# Pizza_BASE.net
KiCad netlist of a schematic drawn in Altium Designer
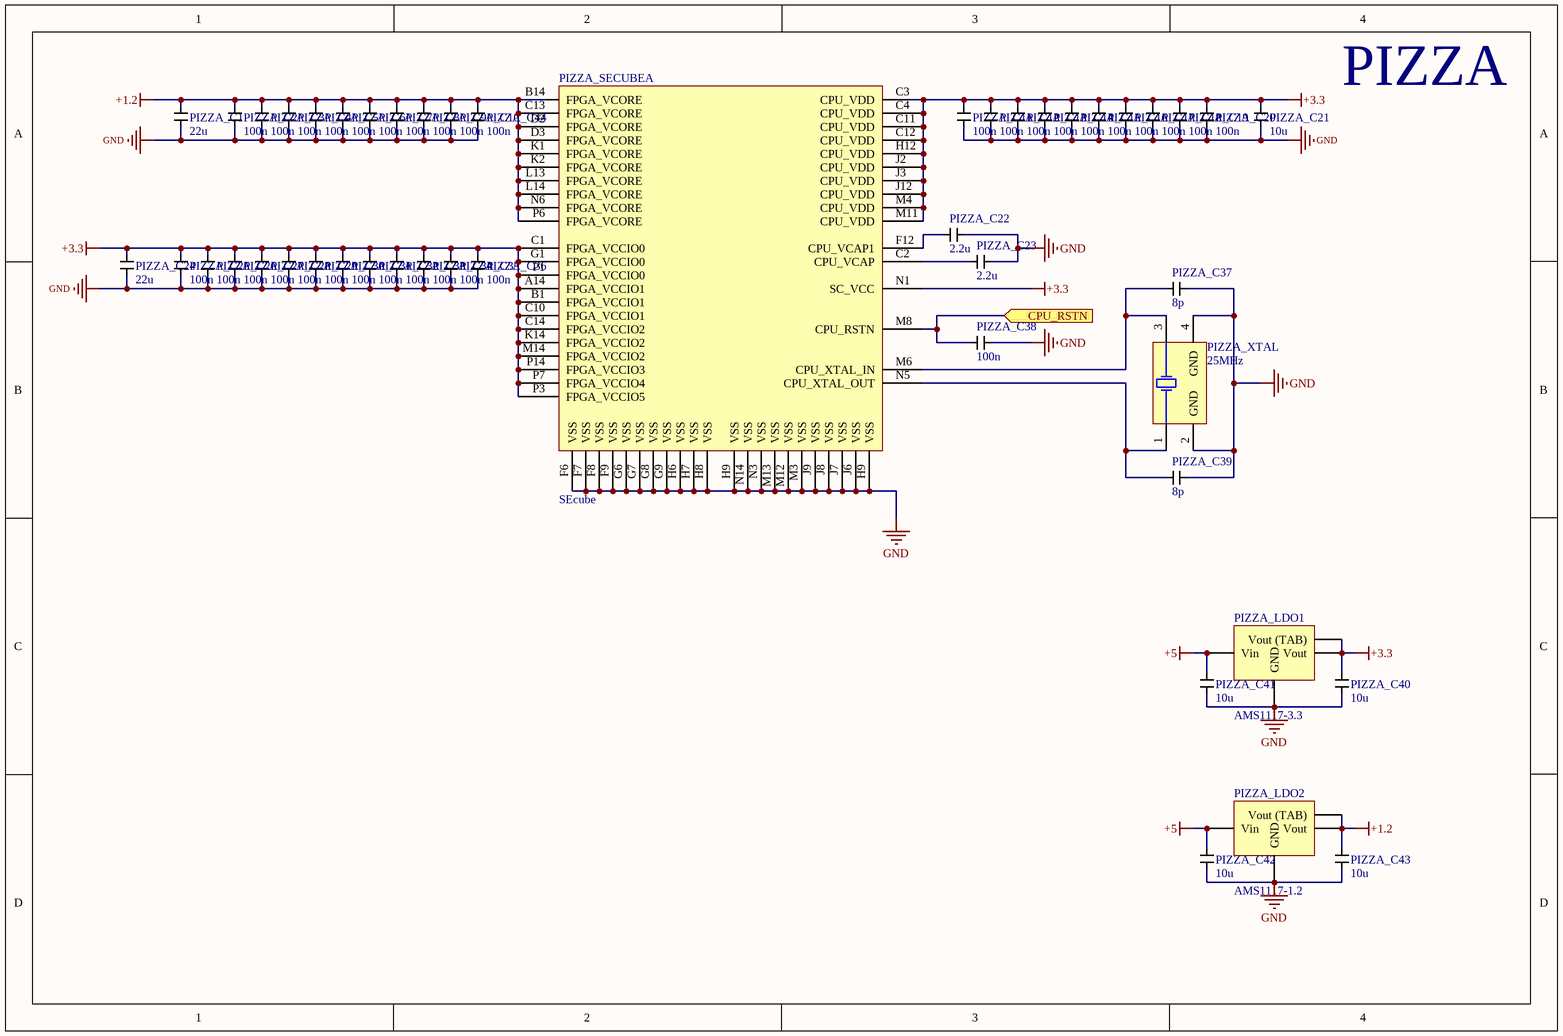
[diagram p0: Pizza BASE.SchDoc]

(export (version "E")
  (design (tool "Eeschema 10.0.6"))
  (components
    (comp (ref "PIZZA_C1") (value "22u") (footprint "C0402") (libsource (lib "ECSC2024") (part "C")))
    (comp (ref "PIZZA_C2") (value "100n") (footprint "C0201") (libsource (lib "ECSC2024") (part "C")))
    (comp (ref "PIZZA_C3") (value "100n") (footprint "C0201") (libsource (lib "ECSC2024") (part "C")))
    (comp (ref "PIZZA_C4") (value "100n") (footprint "C0201") (libsource (lib "ECSC2024") (part "C")))
    (comp (ref "PIZZA_C5") (value "100n") (footprint "C0201") (libsource (lib "ECSC2024") (part "C")))
    (comp (ref "PIZZA_C6") (value "100n") (footprint "C0201") (libsource (lib "ECSC2024") (part "C")))
    (comp (ref "PIZZA_C7") (value "100n") (footprint "C0201") (libsource (lib "ECSC2024") (part "C")))
    (comp (ref "PIZZA_C8") (value "100n") (footprint "C0201") (libsource (lib "ECSC2024") (part "C")))
    (comp (ref "PIZZA_C9") (value "100n") (footprint "C0201") (libsource (lib "ECSC2024") (part "C")))
    (comp (ref "PIZZA_C10") (value "100n") (footprint "C0201") (libsource (lib "ECSC2024") (part "C")))
    (comp (ref "PIZZA_C11") (value "100n") (footprint "C0201") (libsource (lib "ECSC2024") (part "C")))
    (comp (ref "PIZZA_C12") (value "100n") (footprint "C0201") (libsource (lib "ECSC2024") (part "C")))
    (comp (ref "PIZZA_C13") (value "100n") (footprint "C0201") (libsource (lib "ECSC2024") (part "C")))
    (comp (ref "PIZZA_C14") (value "100n") (footprint "C0201") (libsource (lib "ECSC2024") (part "C")))
    (comp (ref "PIZZA_C15") (value "100n") (footprint "C0201") (libsource (lib "ECSC2024") (part "C")))
    (comp (ref "PIZZA_C16") (value "100n") (footprint "C0201") (libsource (lib "ECSC2024") (part "C")))
    (comp (ref "PIZZA_C17") (value "100n") (footprint "C0201") (libsource (lib "ECSC2024") (part "C")))
    (comp (ref "PIZZA_C18") (value "100n") (footprint "C0201") (libsource (lib "ECSC2024") (part "C")))
    (comp (ref "PIZZA_C19") (value "100n") (footprint "C0201") (libsource (lib "ECSC2024") (part "C")))
    (comp (ref "PIZZA_C20") (value "100n") (footprint "C0201") (libsource (lib "ECSC2024") (part "C")))
    (comp (ref "PIZZA_C21") (value "10u") (footprint "C0402") (libsource (lib "ECSC2024") (part "C")))
    (comp (ref "PIZZA_C22") (value "2.2u") (footprint "C0402") (libsource (lib "ECSC2024") (part "C")))
    (comp (ref "PIZZA_C23") (value "2.2u") (footprint "C0402") (libsource (lib "ECSC2024") (part "C")))
    (comp (ref "PIZZA_C24") (value "22u") (footprint "C0402") (libsource (lib "ECSC2024") (part "C")))
    (comp (ref "PIZZA_C25") (value "100n") (footprint "C0201") (libsource (lib "ECSC2024") (part "C")))
    (comp (ref "PIZZA_C26") (value "100n") (footprint "C0201") (libsource (lib "ECSC2024") (part "C")))
    (comp (ref "PIZZA_C27") (value "100n") (footprint "C0201") (libsource (lib "ECSC2024") (part "C")))
    (comp (ref "PIZZA_C28") (value "100n") (footprint "C0201") (libsource (lib "ECSC2024") (part "C")))
    (comp (ref "PIZZA_C29") (value "100n") (footprint "C0201") (libsource (lib "ECSC2024") (part "C")))
    (comp (ref "PIZZA_C30") (value "100n") (footprint "C0201") (libsource (lib "ECSC2024") (part "C")))
    (comp (ref "PIZZA_C31") (value "100n") (footprint "C0201") (libsource (lib "ECSC2024") (part "C")))
    (comp (ref "PIZZA_C32") (value "100n") (footprint "C0201") (libsource (lib "ECSC2024") (part "C")))
    (comp (ref "PIZZA_C33") (value "100n") (footprint "C0201") (libsource (lib "ECSC2024") (part "C")))
    (comp (ref "PIZZA_C34") (value "100n") (footprint "C0201") (libsource (lib "ECSC2024") (part "C")))
    (comp (ref "PIZZA_C35") (value "100n") (footprint "C0201") (libsource (lib "ECSC2024") (part "C")))
    (comp (ref "PIZZA_C36") (value "100n") (footprint "C0201") (libsource (lib "ECSC2024") (part "C")))
    (comp (ref "PIZZA_C37") (value "8p") (footprint "C0402") (libsource (lib "ECSC2024") (part "C")))
    (comp (ref "PIZZA_C38") (value "100n") (footprint "C0201") (libsource (lib "ECSC2024") (part "C")))
    (comp (ref "PIZZA_C39") (value "8p") (footprint "C0402") (libsource (lib "ECSC2024") (part "C")))
    (comp (ref "PIZZA_C40") (value "10u") (footprint "C0402") (libsource (lib "ECSC2024") (part "C")))
    (comp (ref "PIZZA_C41") (value "10u") (footprint "C0402") (libsource (lib "ECSC2024") (part "C")))
    (comp (ref "PIZZA_C42") (value "10u") (footprint "C0402") (libsource (lib "ECSC2024") (part "C")))
    (comp (ref "PIZZA_C43") (value "10u") (footprint "C0402") (libsource (lib "ECSC2024") (part "C")))
    (comp (ref "PIZZA_C44") (value "100n") (footprint "C0201") (libsource (lib "ECSC2024") (part "C")))
    (comp (ref "PIZZA_LDO1")
      (value "AMS1117-3.3")
      (footprint "SOT-223")
      (libsource (lib "ECSC2024") (part "LDO"))
    )
    (comp (ref "PIZZA_LDO2")
      (value "AMS1117-1.2")
      (footprint "SOT-223")
      (libsource (lib "ECSC2024") (part "LDO"))
    )
    (comp (ref "PIZZA_SECUBE")
      (value "SEcube")
      (footprint "SEcube")
      (libsource (lib "ECSC2024") (part "SEcube"))
    )
    (comp (ref "PIZZA_XTAL")
      (value "25MHz")
      (footprint "TSX-3225")
      (libsource (lib "ECSC2024") (part "XTAL"))
    )
  )
  (nets
    (net (code "1") (name "+1.2") (class "Default")
      (node (ref "PIZZA_C1") (pin "2") (pinfunction "2_2") (pintype "passive"))
      (node (ref "PIZZA_C10") (pin "2") (pinfunction "2_2") (pintype "passive"))
      (node (ref "PIZZA_C2") (pin "2") (pinfunction "2_2") (pintype "passive"))
      (node (ref "PIZZA_C3") (pin "2") (pinfunction "2_2") (pintype "passive"))
      (node (ref "PIZZA_C4") (pin "2") (pinfunction "2_2") (pintype "passive"))
      (node (ref "PIZZA_C43") (pin "2") (pinfunction "2_2") (pintype "passive"))
      (node (ref "PIZZA_C44") (pin "2") (pinfunction "2_2") (pintype "passive"))
      (node (ref "PIZZA_C5") (pin "2") (pinfunction "2_2") (pintype "passive"))
      (node (ref "PIZZA_C6") (pin "2") (pinfunction "2_2") (pintype "passive"))
      (node (ref "PIZZA_C7") (pin "2") (pinfunction "2_2") (pintype "passive"))
      (node (ref "PIZZA_C8") (pin "2") (pinfunction "2_2") (pintype "passive"))
      (node (ref "PIZZA_C9") (pin "2") (pinfunction "2_2") (pintype "passive"))
      (node (ref "PIZZA_LDO2") (pin "3") (pinfunction "Vout_3") (pintype "passive"))
      (node (ref "PIZZA_LDO2") (pin "4") (pinfunction "Vout_(TAB)_4") (pintype "passive"))
      (node (ref "PIZZA_SECUBE") (pin "B14") (pinfunction "FPGA_VCORE_B14") (pintype "passive"))
      (node (ref "PIZZA_SECUBE") (pin "C13") (pinfunction "FPGA_VCORE_C13") (pintype "passive"))
      (node (ref "PIZZA_SECUBE") (pin "D2") (pinfunction "FPGA_VCORE_D2") (pintype "passive"))
      (node (ref "PIZZA_SECUBE") (pin "D3") (pinfunction "FPGA_VCORE_D3") (pintype "passive"))
      (node (ref "PIZZA_SECUBE") (pin "K1") (pinfunction "FPGA_VCORE_K1") (pintype "passive"))
      (node (ref "PIZZA_SECUBE") (pin "K2") (pinfunction "FPGA_VCORE_K2") (pintype "passive"))
      (node (ref "PIZZA_SECUBE") (pin "L13") (pinfunction "FPGA_VCORE_L13") (pintype "passive"))
      (node (ref "PIZZA_SECUBE") (pin "L14") (pinfunction "FPGA_VCORE_L14") (pintype "passive"))
      (node (ref "PIZZA_SECUBE") (pin "N6") (pinfunction "FPGA_VCORE_N6") (pintype "passive"))
      (node (ref "PIZZA_SECUBE") (pin "P6") (pinfunction "FPGA_VCORE_P6") (pintype "passive"))
    )
    (net (code "2") (name "+3.3") (class "Default")
      (node (ref "PIZZA_C11") (pin "2") (pinfunction "2_2") (pintype "passive"))
      (node (ref "PIZZA_C12") (pin "2") (pinfunction "2_2") (pintype "passive"))
      (node (ref "PIZZA_C13") (pin "2") (pinfunction "2_2") (pintype "passive"))
      (node (ref "PIZZA_C14") (pin "2") (pinfunction "2_2") (pintype "passive"))
      (node (ref "PIZZA_C15") (pin "2") (pinfunction "2_2") (pintype "passive"))
      (node (ref "PIZZA_C16") (pin "2") (pinfunction "2_2") (pintype "passive"))
      (node (ref "PIZZA_C17") (pin "2") (pinfunction "2_2") (pintype "passive"))
      (node (ref "PIZZA_C18") (pin "2") (pinfunction "2_2") (pintype "passive"))
      (node (ref "PIZZA_C19") (pin "2") (pinfunction "2_2") (pintype "passive"))
      (node (ref "PIZZA_C20") (pin "2") (pinfunction "2_2") (pintype "passive"))
      (node (ref "PIZZA_C21") (pin "2") (pinfunction "2_2") (pintype "passive"))
      (node (ref "PIZZA_C24") (pin "2") (pinfunction "2_2") (pintype "passive"))
      (node (ref "PIZZA_C25") (pin "2") (pinfunction "2_2") (pintype "passive"))
      (node (ref "PIZZA_C26") (pin "2") (pinfunction "2_2") (pintype "passive"))
      (node (ref "PIZZA_C27") (pin "2") (pinfunction "2_2") (pintype "passive"))
      (node (ref "PIZZA_C28") (pin "2") (pinfunction "2_2") (pintype "passive"))
      (node (ref "PIZZA_C29") (pin "2") (pinfunction "2_2") (pintype "passive"))
      (node (ref "PIZZA_C30") (pin "2") (pinfunction "2_2") (pintype "passive"))
      (node (ref "PIZZA_C31") (pin "2") (pinfunction "2_2") (pintype "passive"))
      (node (ref "PIZZA_C32") (pin "2") (pinfunction "2_2") (pintype "passive"))
      (node (ref "PIZZA_C33") (pin "2") (pinfunction "2_2") (pintype "passive"))
      (node (ref "PIZZA_C34") (pin "2") (pinfunction "2_2") (pintype "passive"))
      (node (ref "PIZZA_C35") (pin "2") (pinfunction "2_2") (pintype "passive"))
      (node (ref "PIZZA_C36") (pin "2") (pinfunction "2_2") (pintype "passive"))
      (node (ref "PIZZA_C40") (pin "2") (pinfunction "2_2") (pintype "passive"))
      (node (ref "PIZZA_LDO1") (pin "3") (pinfunction "Vout_3") (pintype "passive"))
      (node (ref "PIZZA_LDO1") (pin "4") (pinfunction "Vout_(TAB)_4") (pintype "passive"))
      (node (ref "PIZZA_SECUBE") (pin "A14") (pinfunction "FPGA_VCCIO1_A14") (pintype "passive"))
      (node (ref "PIZZA_SECUBE") (pin "B1") (pinfunction "FPGA_VCCIO1_B1") (pintype "passive"))
      (node (ref "PIZZA_SECUBE") (pin "C1") (pinfunction "FPGA_VCCIO0_C1") (pintype "passive"))
      (node (ref "PIZZA_SECUBE") (pin "C10") (pinfunction "FPGA_VCCIO1_C10") (pintype "passive"))
      (node (ref "PIZZA_SECUBE") (pin "C11") (pinfunction "CPU_VDD_C11") (pintype "passive"))
      (node (ref "PIZZA_SECUBE") (pin "C12") (pinfunction "CPU_VDD_C12") (pintype "passive"))
      (node (ref "PIZZA_SECUBE") (pin "C14") (pinfunction "FPGA_VCCIO2_C14") (pintype "passive"))
      (node (ref "PIZZA_SECUBE") (pin "C3") (pinfunction "CPU_VDD_C3") (pintype "passive"))
      (node (ref "PIZZA_SECUBE") (pin "C4") (pinfunction "CPU_VDD_C4") (pintype "passive"))
      (node (ref "PIZZA_SECUBE") (pin "G1") (pinfunction "FPGA_VCCIO0_G1") (pintype "passive"))
      (node (ref "PIZZA_SECUBE") (pin "H12") (pinfunction "CPU_VDD_H12") (pintype "passive"))
      (node (ref "PIZZA_SECUBE") (pin "J12") (pinfunction "CPU_VDD_J12") (pintype "passive"))
      (node (ref "PIZZA_SECUBE") (pin "J2") (pinfunction "CPU_VDD_J2") (pintype "passive"))
      (node (ref "PIZZA_SECUBE") (pin "J3") (pinfunction "CPU_VDD_J3") (pintype "passive"))
      (node (ref "PIZZA_SECUBE") (pin "K14") (pinfunction "FPGA_VCCIO2_K14") (pintype "passive"))
      (node (ref "PIZZA_SECUBE") (pin "M11") (pinfunction "CPU_VDD_M11") (pintype "passive"))
      (node (ref "PIZZA_SECUBE") (pin "M14") (pinfunction "FPGA_VCCIO2_M14") (pintype "passive"))
      (node (ref "PIZZA_SECUBE") (pin "M4") (pinfunction "CPU_VDD_M4") (pintype "passive"))
      (node (ref "PIZZA_SECUBE") (pin "N1") (pinfunction "SC_VCC_N1") (pintype "passive"))
      (node (ref "PIZZA_SECUBE") (pin "P1") (pinfunction "FPGA_VCCIO0_P1") (pintype "passive"))
      (node (ref "PIZZA_SECUBE") (pin "P14") (pinfunction "FPGA_VCCIO3_P14") (pintype "passive"))
      (node (ref "PIZZA_SECUBE") (pin "P3") (pinfunction "FPGA_VCCIO5_P3") (pintype "passive"))
      (node (ref "PIZZA_SECUBE") (pin "P7") (pinfunction "FPGA_VCCIO4_P7") (pintype "passive"))
    )
    (net (code "3") (name "+5") (class "Default")
      (node (ref "PIZZA_C41") (pin "2") (pinfunction "2_2") (pintype "passive"))
      (node (ref "PIZZA_C42") (pin "2") (pinfunction "2_2") (pintype "passive"))
      (node (ref "PIZZA_LDO1") (pin "2") (pinfunction "Vin_2") (pintype "passive"))
      (node (ref "PIZZA_LDO2") (pin "2") (pinfunction "Vin_2") (pintype "passive"))
    )
    (net (code "4") (name "/CPU_RSTN") (class "Default")
      (node (ref "PIZZA_C38") (pin "2") (pinfunction "2_2") (pintype "passive"))
      (node (ref "PIZZA_SECUBE") (pin "M8") (pinfunction "CPU_RSTN_M8") (pintype "passive"))
    )
    (net (code "5") (name "GND") (class "Default")
      (node (ref "PIZZA_C1") (pin "1") (pinfunction "1_1") (pintype "passive"))
      (node (ref "PIZZA_C10") (pin "1") (pinfunction "1_1") (pintype "passive"))
      (node (ref "PIZZA_C11") (pin "1") (pinfunction "1_1") (pintype "passive"))
      (node (ref "PIZZA_C12") (pin "1") (pinfunction "1_1") (pintype "passive"))
      (node (ref "PIZZA_C13") (pin "1") (pinfunction "1_1") (pintype "passive"))
      (node (ref "PIZZA_C14") (pin "1") (pinfunction "1_1") (pintype "passive"))
      (node (ref "PIZZA_C15") (pin "1") (pinfunction "1_1") (pintype "passive"))
      (node (ref "PIZZA_C16") (pin "1") (pinfunction "1_1") (pintype "passive"))
      (node (ref "PIZZA_C17") (pin "1") (pinfunction "1_1") (pintype "passive"))
      (node (ref "PIZZA_C18") (pin "1") (pinfunction "1_1") (pintype "passive"))
      (node (ref "PIZZA_C19") (pin "1") (pinfunction "1_1") (pintype "passive"))
      (node (ref "PIZZA_C2") (pin "1") (pinfunction "1_1") (pintype "passive"))
      (node (ref "PIZZA_C20") (pin "1") (pinfunction "1_1") (pintype "passive"))
      (node (ref "PIZZA_C21") (pin "1") (pinfunction "1_1") (pintype "passive"))
      (node (ref "PIZZA_C22") (pin "1") (pinfunction "1_1") (pintype "passive"))
      (node (ref "PIZZA_C23") (pin "1") (pinfunction "1_1") (pintype "passive"))
      (node (ref "PIZZA_C24") (pin "1") (pinfunction "1_1") (pintype "passive"))
      (node (ref "PIZZA_C25") (pin "1") (pinfunction "1_1") (pintype "passive"))
      (node (ref "PIZZA_C26") (pin "1") (pinfunction "1_1") (pintype "passive"))
      (node (ref "PIZZA_C27") (pin "1") (pinfunction "1_1") (pintype "passive"))
      (node (ref "PIZZA_C28") (pin "1") (pinfunction "1_1") (pintype "passive"))
      (node (ref "PIZZA_C29") (pin "1") (pinfunction "1_1") (pintype "passive"))
      (node (ref "PIZZA_C3") (pin "1") (pinfunction "1_1") (pintype "passive"))
      (node (ref "PIZZA_C30") (pin "1") (pinfunction "1_1") (pintype "passive"))
      (node (ref "PIZZA_C31") (pin "1") (pinfunction "1_1") (pintype "passive"))
      (node (ref "PIZZA_C32") (pin "1") (pinfunction "1_1") (pintype "passive"))
      (node (ref "PIZZA_C33") (pin "1") (pinfunction "1_1") (pintype "passive"))
      (node (ref "PIZZA_C34") (pin "1") (pinfunction "1_1") (pintype "passive"))
      (node (ref "PIZZA_C35") (pin "1") (pinfunction "1_1") (pintype "passive"))
      (node (ref "PIZZA_C36") (pin "1") (pinfunction "1_1") (pintype "passive"))
      (node (ref "PIZZA_C37") (pin "2") (pinfunction "2_2") (pintype "passive"))
      (node (ref "PIZZA_C38") (pin "1") (pinfunction "1_1") (pintype "passive"))
      (node (ref "PIZZA_C39") (pin "2") (pinfunction "2_2") (pintype "passive"))
      (node (ref "PIZZA_C4") (pin "1") (pinfunction "1_1") (pintype "passive"))
      (node (ref "PIZZA_C40") (pin "1") (pinfunction "1_1") (pintype "passive"))
      (node (ref "PIZZA_C41") (pin "1") (pinfunction "1_1") (pintype "passive"))
      (node (ref "PIZZA_C42") (pin "1") (pinfunction "1_1") (pintype "passive"))
      (node (ref "PIZZA_C43") (pin "1") (pinfunction "1_1") (pintype "passive"))
      (node (ref "PIZZA_C44") (pin "1") (pinfunction "1_1") (pintype "passive"))
      (node (ref "PIZZA_C5") (pin "1") (pinfunction "1_1") (pintype "passive"))
      (node (ref "PIZZA_C6") (pin "1") (pinfunction "1_1") (pintype "passive"))
      (node (ref "PIZZA_C7") (pin "1") (pinfunction "1_1") (pintype "passive"))
      (node (ref "PIZZA_C8") (pin "1") (pinfunction "1_1") (pintype "passive"))
      (node (ref "PIZZA_C9") (pin "1") (pinfunction "1_1") (pintype "passive"))
      (node (ref "PIZZA_LDO1") (pin "1") (pinfunction "GND_1") (pintype "passive"))
      (node (ref "PIZZA_LDO2") (pin "1") (pinfunction "GND_1") (pintype "passive"))
      (node (ref "PIZZA_SECUBE") (pin "F6") (pinfunction "VSS_F6") (pintype "passive"))
      (node (ref "PIZZA_SECUBE") (pin "F7") (pinfunction "VSS_F7") (pintype "passive"))
      (node (ref "PIZZA_SECUBE") (pin "F8") (pinfunction "VSS_F8") (pintype "passive"))
      (node (ref "PIZZA_SECUBE") (pin "F9") (pinfunction "VSS_F9") (pintype "passive"))
      (node (ref "PIZZA_SECUBE") (pin "G6") (pinfunction "VSS_G6") (pintype "passive"))
      (node (ref "PIZZA_SECUBE") (pin "G7") (pinfunction "VSS_G7") (pintype "passive"))
      (node (ref "PIZZA_SECUBE") (pin "G8") (pinfunction "VSS_G8") (pintype "passive"))
      (node (ref "PIZZA_SECUBE") (pin "G9") (pinfunction "VSS_G9") (pintype "passive"))
      (node (ref "PIZZA_SECUBE") (pin "H6") (pinfunction "VSS_H6") (pintype "passive"))
      (node (ref "PIZZA_SECUBE") (pin "H7") (pinfunction "VSS_H7") (pintype "passive"))
      (node (ref "PIZZA_SECUBE") (pin "H8") (pinfunction "VSS_H8") (pintype "passive"))
      (node (ref "PIZZA_SECUBE") (pin "H9") (pinfunction "VSS_H9") (pintype "passive"))
      (node (ref "PIZZA_SECUBE") (pin "J6") (pinfunction "VSS_J6") (pintype "passive"))
      (node (ref "PIZZA_SECUBE") (pin "J7") (pinfunction "VSS_J7") (pintype "passive"))
      (node (ref "PIZZA_SECUBE") (pin "J8") (pinfunction "VSS_J8") (pintype "passive"))
      (node (ref "PIZZA_SECUBE") (pin "J9") (pinfunction "VSS_J9") (pintype "passive"))
      (node (ref "PIZZA_SECUBE") (pin "M12") (pinfunction "VSS_M12") (pintype "passive"))
      (node (ref "PIZZA_SECUBE") (pin "M13") (pinfunction "VSS_M13") (pintype "passive"))
      (node (ref "PIZZA_SECUBE") (pin "M3") (pinfunction "VSS_M3") (pintype "passive"))
      (node (ref "PIZZA_SECUBE") (pin "N14") (pinfunction "VSS_N14") (pintype "passive"))
      (node (ref "PIZZA_SECUBE") (pin "N3") (pinfunction "VSS_N3") (pintype "passive"))
      (node (ref "PIZZA_XTAL") (pin "2") (pinfunction "GND_2") (pintype "power_in"))
      (node (ref "PIZZA_XTAL") (pin "4") (pinfunction "GND_4") (pintype "power_in"))
    )
    (net (code "6") (name "Net-(PIZZA_SECUBEA-CPU_VCAP)") (class "Default")
      (node (ref "PIZZA_C23") (pin "2") (pinfunction "2_2") (pintype "passive"))
      (node (ref "PIZZA_SECUBE") (pin "C2") (pinfunction "CPU_VCAP_C2") (pintype "passive"))
    )
    (net (code "7") (name "Net-(PIZZA_SECUBEA-CPU_VCAP1)") (class "Default")
      (node (ref "PIZZA_C22") (pin "2") (pinfunction "2_2") (pintype "passive"))
      (node (ref "PIZZA_SECUBE") (pin "F12") (pinfunction "CPU_VCAP1_F12") (pintype "passive"))
    )
    (net (code "8") (name "Net-(PIZZA_SECUBEA-CPU_XTAL_IN)") (class "Default")
      (node (ref "PIZZA_C37") (pin "1") (pinfunction "1_1") (pintype "passive"))
      (node (ref "PIZZA_SECUBE") (pin "M6") (pinfunction "CPU_XTAL_IN_M6") (pintype "passive"))
      (node (ref "PIZZA_XTAL") (pin "3") (pinfunction "X2_3") (pintype "passive"))
    )
    (net (code "9") (name "Net-(PIZZA_SECUBEA-CPU_XTAL_OUT)") (class "Default")
      (node (ref "PIZZA_C39") (pin "1") (pinfunction "1_1") (pintype "passive"))
      (node (ref "PIZZA_SECUBE") (pin "N5") (pinfunction "CPU_XTAL_OUT_N5") (pintype "passive"))
      (node (ref "PIZZA_XTAL") (pin "1") (pinfunction "X1_1") (pintype "passive"))
    )
  )
)
